# 009pcb6.net
KiCad netlist of a schematic drawn in EAGLE
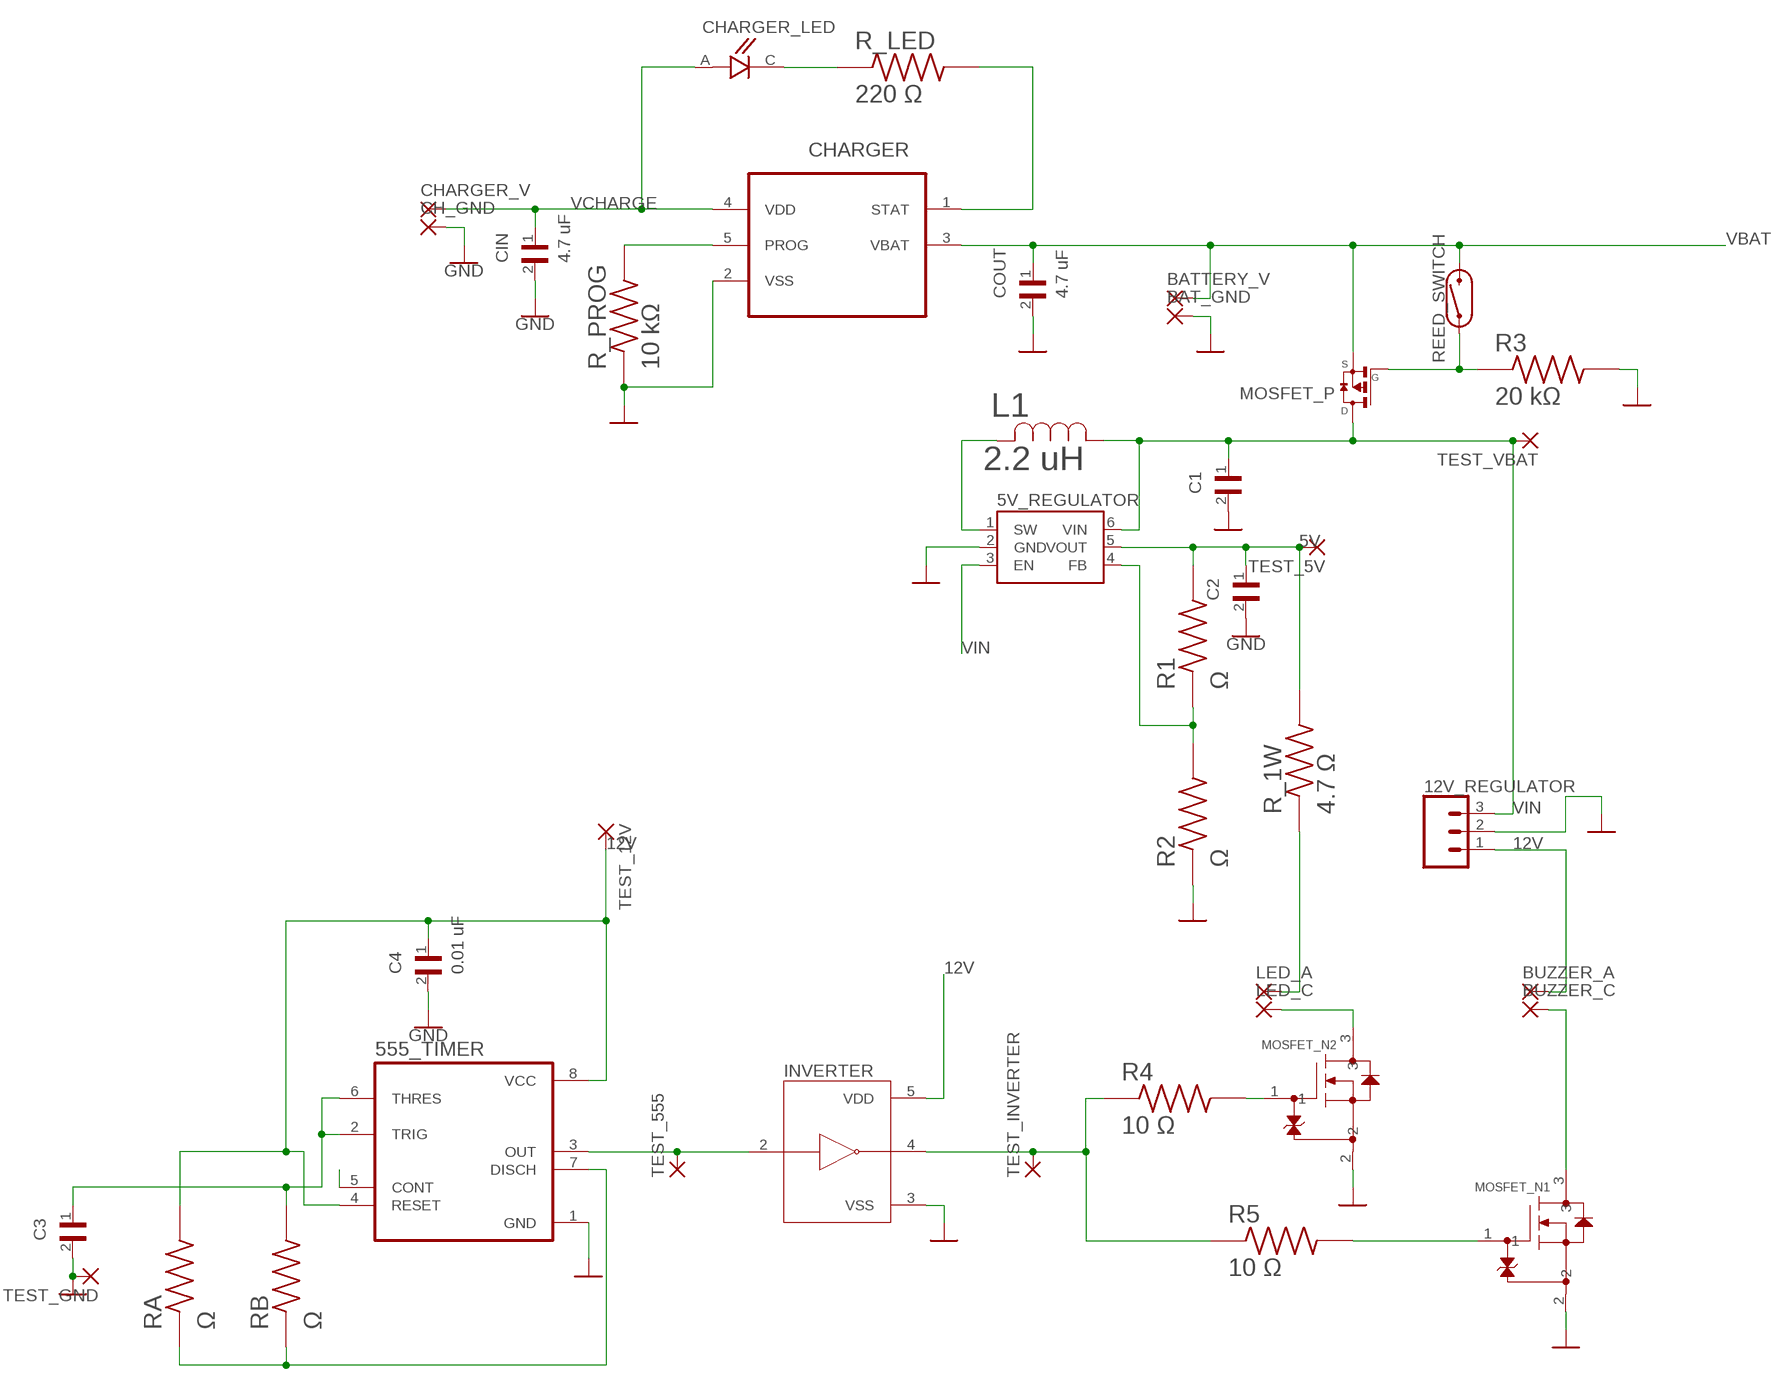
[diagram p0: schematic, sheet 1]

(export (version "E")
  (design (tool "Eeschema 10.0.6"))
  (components
    (comp (ref "5V_REGULATOR")
      (value "TLV61070ASOT-23")
      (footprint "eagle-import:SOT23-6")
      (libsource (lib "eagle-import") (part "TLV61070ASOT-23"))
    )
    (comp (ref "12V_REGULATOR")
      (value "CONN_03")
      (footprint "eagle-import:1X03")
      (libsource (lib "eagle-import") (part "CONN_03"))
    )
    (comp (ref "555_TIMER")
      (value "NE555DR")
      (footprint "eagle-import:SOIC127P599X175-8N")
      (fields (field (name "MF") "Texas Instruments"))
      (libsource (lib "eagle-import") (part "NE555DR"))
    )
    (comp (ref "BATTERY_V")
      (value "WIREPADSMD1,27-254")
      (footprint "eagle-import:SMD1,27-2,54")
      (libsource (lib "eagle-import") (part "WIREPADSMD1,27-254"))
    )
    (comp (ref "BAT_GND")
      (value "WIREPADSMD1,27-254")
      (footprint "eagle-import:SMD1,27-2,54")
      (libsource (lib "eagle-import") (part "WIREPADSMD1,27-254"))
    )
    (comp (ref "BUZZER_A")
      (value "WIREPADSMD1,27-254")
      (footprint "eagle-import:SMD1,27-2,54")
      (libsource (lib "eagle-import") (part "WIREPADSMD1,27-254"))
    )
    (comp (ref "BUZZER_C")
      (value "WIREPADSMD1,27-254")
      (footprint "eagle-import:SMD1,27-2,54")
      (libsource (lib "eagle-import") (part "WIREPADSMD1,27-254"))
    )
    (comp (ref "C1")
      (value "GRT21BR61H475ME13L")
      (footprint "eagle-import:CAPC2012X135N")
      (fields (field (name "MF") "Murata Electronics"))
      (libsource (lib "eagle-import") (part "GRT21BR61H475ME13L"))
    )
    (comp (ref "C2")
      (value "GRT21BR61H475ME13L")
      (footprint "eagle-import:CAPC2012X135N")
      (fields (field (name "MF") "Murata Electronics"))
      (libsource (lib "eagle-import") (part "GRT21BR61H475ME13L"))
    )
    (comp (ref "C3")
      (value "GRT21BR61H475ME13L")
      (footprint "eagle-import:CAPC2012X135N")
      (fields (field (name "MF") "Murata Electronics"))
      (libsource (lib "eagle-import") (part "GRT21BR61H475ME13L"))
    )
    (comp (ref "C4")
      (value "0.01 uF")
      (footprint "eagle-import:CAPC2012X135N")
      (fields (field (name "MF") "Murata Electronics") (field (name "MP") "GRT21BR61H475ME13L"))
      (libsource (lib "eagle-import") (part "GRT21BR61H475ME13L"))
    )
    (comp (ref "CHARGER")
      (value "MCP73831T-5ACI/OT")
      (footprint "eagle-import:SOT95P280X145-5N")
      (fields
        (field (name "DIGI-KEY_PART_NUMBER") "MCP73831T-5ACI/OTTR-ND")
        (field (name "MF") "Microchip Technology")
      )
      (libsource (lib "eagle-import") (part "MCP73831T-5ACI/OT"))
    )
    (comp (ref "CHARGER_LED")
      (value "5988170107F")
      (footprint "eagle-import:LEDC2012X70N")
      (fields (field (name "MF") "Dialight"))
      (libsource (lib "eagle-import") (part "5988170107F"))
    )
    (comp (ref "CHARGER_V")
      (value "WIREPADSMD1,27-254")
      (footprint "eagle-import:SMD1,27-2,54")
      (libsource (lib "eagle-import") (part "WIREPADSMD1,27-254"))
    )
    (comp (ref "CH_GND")
      (value "WIREPADSMD1,27-254")
      (footprint "eagle-import:SMD1,27-2,54")
      (libsource (lib "eagle-import") (part "WIREPADSMD1,27-254"))
    )
    (comp (ref "CIN")
      (value "4.7 uF")
      (footprint "eagle-import:CAPC2012X135N")
      (fields (field (name "MF") "Murata Electronics") (field (name "MP") "GRT21BR61H475ME13L"))
      (libsource (lib "eagle-import") (part "GRT21BR61H475ME13L"))
    )
    (comp (ref "COUT")
      (value "4.7 uF")
      (footprint "eagle-import:CAPC2012X135N")
      (fields (field (name "MF") "Murata Electronics") (field (name "MP") "GRT21BR61H475ME13L"))
      (libsource (lib "eagle-import") (part "GRT21BR61H475ME13L"))
    )
    (comp (ref "INVERTER")
      (value "BU4SU69G2-TR")
      (footprint "eagle-import:SOT95P280X125-5N")
      (fields (field (name "MF") "Rohm"))
      (libsource (lib "eagle-import") (part "BU4SU69G2-TR"))
    )
    (comp (ref "L1")
      (value "2.2 uH")
      (footprint "eagle-import:IND_8357022_WRE")
      (fields
        (field (name "MANUFACTURER_PART_NUMBER") "74438357022")
        (field (name "COPYRIGHT") "Copyright (C) 2022 Ultra Librarian. All rights reserved.")
      )
      (libsource (lib "eagle-import") (part "74438357022"))
    )
    (comp (ref "LED_A")
      (value "WIREPADSMD1,27-254")
      (footprint "eagle-import:SMD1,27-2,54")
      (libsource (lib "eagle-import") (part "WIREPADSMD1,27-254"))
    )
    (comp (ref "LED_C")
      (value "WIREPADSMD1,27-254")
      (footprint "eagle-import:SMD1,27-2,54")
      (libsource (lib "eagle-import") (part "WIREPADSMD1,27-254"))
    )
    (comp (ref "MOSFET_N1")
      (value "SSM3K335R")
      (footprint "eagle-import:SOT-23F_TOS")
      (fields (field (name "COPYRIGHT") "Copyright (C) 2022 Ultra Librarian. All rights reserved."))
      (libsource (lib "eagle-import") (part "SSM3K335R"))
    )
    (comp (ref "MOSFET_N2")
      (value "SSM3K335R")
      (footprint "eagle-import:SOT-23F_TOS")
      (fields (field (name "COPYRIGHT") "Copyright (C) 2022 Ultra Librarian. All rights reserved."))
      (libsource (lib "eagle-import") (part "SSM3K335R"))
    )
    (comp (ref "MOSFET_P")
      (value "DMP2004K")
      (footprint "eagle-import:SOT23")
      (fields (field (name "MF") "Diodes Zetex"))
      (libsource (lib "eagle-import") (part "DMP2004K"))
    )
    (comp (ref "R1")
      (value "Ω")
      (footprint "eagle-import:RESC2012X60N")
      (fields
        (field (name "DIGI-KEY_PART_NUMBER") "311-20KARTR-ND")
        (field (name "MF") "Yageo")
        (field (name "MP") "RC0805JR-0720KL")
      )
      (libsource (lib "eagle-import") (part "RC0805JR-0720KL"))
    )
    (comp (ref "R2")
      (value "Ω")
      (footprint "eagle-import:RESC2012X60N")
      (fields
        (field (name "DIGI-KEY_PART_NUMBER") "311-20KARTR-ND")
        (field (name "MF") "Yageo")
        (field (name "MP") "RC0805JR-0720KL")
      )
      (libsource (lib "eagle-import") (part "RC0805JR-0720KL"))
    )
    (comp (ref "R3")
      (value "20 kΩ")
      (footprint "eagle-import:RESC2012X60N")
      (fields
        (field (name "DIGI-KEY_PART_NUMBER") "311-20KARTR-ND")
        (field (name "MF") "Yageo")
        (field (name "MP") "RC0805JR-0720KL")
      )
      (libsource (lib "eagle-import") (part "RC0805JR-0720KL"))
    )
    (comp (ref "R4")
      (value "10 Ω")
      (footprint "eagle-import:RESC2012X60N")
      (fields
        (field (name "DIGI-KEY_PART_NUMBER") "311-20KARTR-ND")
        (field (name "MF") "Yageo")
        (field (name "MP") "RC0805JR-0720KL")
      )
      (libsource (lib "eagle-import") (part "RC0805JR-0720KL"))
    )
    (comp (ref "R5")
      (value "10 Ω")
      (footprint "eagle-import:RESC2012X60N")
      (fields
        (field (name "DIGI-KEY_PART_NUMBER") "311-20KARTR-ND")
        (field (name "MF") "Yageo")
        (field (name "MP") "RC0805JR-0720KL")
      )
      (libsource (lib "eagle-import") (part "RC0805JR-0720KL"))
    )
    (comp (ref "RA")
      (value "Ω")
      (footprint "eagle-import:RESC2012X60N")
      (fields
        (field (name "DIGI-KEY_PART_NUMBER") "311-20KARTR-ND")
        (field (name "MF") "Yageo")
        (field (name "MP") "RC0805JR-0720KL")
      )
      (libsource (lib "eagle-import") (part "RC0805JR-0720KL"))
    )
    (comp (ref "RB")
      (value "Ω")
      (footprint "eagle-import:RESC2012X60N")
      (fields
        (field (name "DIGI-KEY_PART_NUMBER") "311-20KARTR-ND")
        (field (name "MF") "Yageo")
        (field (name "MP") "RC0805JR-0720KL")
      )
      (libsource (lib "eagle-import") (part "RC0805JR-0720KL"))
    )
    (comp (ref "REED_SWITCH")
      (value "REED_SWITCH-PTH-GLASS")
      (footprint "eagle-import:REED_SWITCH_GLASS")
      (libsource (lib "eagle-import") (part "REED_SWITCH-PTH-GLASS"))
    )
    (comp (ref "R_1W")
      (value "4.7 Ω")
      (footprint "eagle-import:RESC6331X65N")
      (fields
        (field (name "DIGI-KEY_PART_NUMBER") "13-RC2512FK-074R7LTR-ND")
        (field (name "MF") "Yageo")
        (field (name "MP") "RC2512FK-074R7L")
      )
      (libsource (lib "eagle-import") (part "RC2512FK-074R7L"))
    )
    (comp (ref "R_LED")
      (value "220 Ω")
      (footprint "eagle-import:RESC2012X60N")
      (fields
        (field (name "DIGI-KEY_PART_NUMBER") "311-20KARTR-ND")
        (field (name "MF") "Yageo")
        (field (name "MP") "RC0805JR-0720KL")
      )
      (libsource (lib "eagle-import") (part "RC0805JR-0720KL"))
    )
    (comp (ref "R_PROG")
      (value "10 kΩ")
      (footprint "eagle-import:RESC2012X60N")
      (fields
        (field (name "DIGI-KEY_PART_NUMBER") "311-20KARTR-ND")
        (field (name "MF") "Yageo")
        (field (name "MP") "RC0805JR-0720KL")
      )
      (libsource (lib "eagle-import") (part "RC0805JR-0720KL"))
    )
    (comp (ref "TEST_5V")
      (value "WIREPADSMD1,27-254")
      (footprint "eagle-import:SMD1,27-2,54")
      (libsource (lib "eagle-import") (part "WIREPADSMD1,27-254"))
    )
    (comp (ref "TEST_12V")
      (value "WIREPADSMD1,27-254")
      (footprint "eagle-import:SMD1,27-2,54")
      (libsource (lib "eagle-import") (part "WIREPADSMD1,27-254"))
    )
    (comp (ref "TEST_555")
      (value "WIREPADSMD1,27-254")
      (footprint "eagle-import:SMD1,27-2,54")
      (libsource (lib "eagle-import") (part "WIREPADSMD1,27-254"))
    )
    (comp (ref "TEST_GND")
      (value "WIREPADSMD1,27-254")
      (footprint "eagle-import:SMD1,27-2,54")
      (libsource (lib "eagle-import") (part "WIREPADSMD1,27-254"))
    )
    (comp (ref "TEST_INVERTER")
      (value "WIREPADSMD1,27-254")
      (footprint "eagle-import:SMD1,27-2,54")
      (libsource (lib "eagle-import") (part "WIREPADSMD1,27-254"))
    )
    (comp (ref "TEST_VBAT")
      (value "WIREPADSMD1,27-254")
      (footprint "eagle-import:SMD1,27-2,54")
      (libsource (lib "eagle-import") (part "WIREPADSMD1,27-254"))
    )
  )
  (nets
    (net (code "1") (name "/5V") (class "Default")
      (node (ref "5V_REGULATOR") (pin "5") (pinfunction "VOUT_5") (pintype "bidirectional"))
      (node (ref "C2") (pin "1") (pinfunction "1_1") (pintype "passive"))
      (node (ref "R1") (pin "2") (pinfunction "2_2") (pintype "passive"))
      (node (ref "R_1W") (pin "2") (pinfunction "2_2") (pintype "passive"))
      (node (ref "TEST_5V") (pin "1") (pinfunction "P_1") (pintype "passive"))
    )
    (net (code "2") (name "/12V") (class "Default")
      (node (ref "12V_REGULATOR") (pin "1") (pinfunction "1_1") (pintype "passive"))
      (node (ref "555_TIMER") (pin "4") (pinfunction "RESET_4") (pintype "input"))
      (node (ref "555_TIMER") (pin "8") (pinfunction "VCC_8") (pintype "power_in"))
      (node (ref "BUZZER_A") (pin "1") (pinfunction "P_1") (pintype "passive"))
      (node (ref "C4") (pin "1") (pinfunction "1_1") (pintype "passive"))
      (node (ref "INVERTER") (pin "5") (pinfunction "VDD_5") (pintype "power_in"))
      (node (ref "RA") (pin "2") (pinfunction "2_2") (pintype "passive"))
      (node (ref "TEST_12V") (pin "1") (pinfunction "P_1") (pintype "passive"))
    )
    (net (code "3") (name "/VBAT") (class "Default")
      (node (ref "BATTERY_V") (pin "1") (pinfunction "P_1") (pintype "passive"))
      (node (ref "CHARGER") (pin "3") (pinfunction "VBAT_3") (pintype "output"))
      (node (ref "COUT") (pin "1") (pinfunction "1_1") (pintype "passive"))
      (node (ref "MOSFET_P") (pin "2") (pinfunction "S_2") (pintype "passive"))
      (node (ref "REED_SWITCH") (pin "P$2") (pinfunction "2_P$2") (pintype "passive"))
    )
    (net (code "4") (name "/VCHARGE") (class "Default")
      (node (ref "CHARGER") (pin "4") (pinfunction "VDD_4") (pintype "power_in"))
      (node (ref "CHARGER_LED") (pin "A") (pinfunction "A_A") (pintype "passive"))
      (node (ref "CHARGER_V") (pin "1") (pinfunction "P_1") (pintype "passive"))
      (node (ref "CIN") (pin "1") (pinfunction "1_1") (pintype "passive"))
    )
    (net (code "5") (name "/VIN") (class "Default")
      (node (ref "12V_REGULATOR") (pin "3") (pinfunction "3_3") (pintype "passive"))
      (node (ref "5V_REGULATOR") (pin "3") (pinfunction "EN_3") (pintype "bidirectional"))
      (node (ref "5V_REGULATOR") (pin "6") (pinfunction "VIN_6") (pintype "bidirectional"))
      (node (ref "C1") (pin "1") (pinfunction "1_1") (pintype "passive"))
      (node (ref "L1") (pin "1") (pinfunction "1_1") (pintype "passive"))
      (node (ref "MOSFET_P") (pin "3") (pinfunction "D_3") (pintype "passive"))
      (node (ref "TEST_VBAT") (pin "1") (pinfunction "P_1") (pintype "passive"))
    )
    (net (code "6") (name "GND") (class "Default")
      (node (ref "12V_REGULATOR") (pin "2") (pinfunction "2_2") (pintype "passive"))
      (node (ref "555_TIMER") (pin "1") (pinfunction "GND_1") (pintype "power_in"))
      (node (ref "5V_REGULATOR") (pin "2") (pinfunction "GND_2") (pintype "bidirectional"))
      (node (ref "BAT_GND") (pin "1") (pinfunction "P_1") (pintype "passive"))
      (node (ref "C1") (pin "2") (pinfunction "2_2") (pintype "passive"))
      (node (ref "C2") (pin "2") (pinfunction "2_2") (pintype "passive"))
      (node (ref "C3") (pin "2") (pinfunction "2_2") (pintype "passive"))
      (node (ref "C4") (pin "2") (pinfunction "2_2") (pintype "passive"))
      (node (ref "CHARGER") (pin "2") (pinfunction "VSS_2") (pintype "power_in"))
      (node (ref "CH_GND") (pin "1") (pinfunction "P_1") (pintype "passive"))
      (node (ref "CIN") (pin "2") (pinfunction "2_2") (pintype "passive"))
      (node (ref "COUT") (pin "2") (pinfunction "2_2") (pintype "passive"))
      (node (ref "INVERTER") (pin "3") (pinfunction "VSS_3") (pintype "power_in"))
      (node (ref "MOSFET_N1") (pin "2") (pinfunction "2_2") (pintype "passive"))
      (node (ref "MOSFET_N2") (pin "2") (pinfunction "2_2") (pintype "passive"))
      (node (ref "R2") (pin "1") (pinfunction "1_1") (pintype "passive"))
      (node (ref "R3") (pin "2") (pinfunction "2_2") (pintype "passive"))
      (node (ref "R_PROG") (pin "1") (pinfunction "1_1") (pintype "passive"))
      (node (ref "TEST_GND") (pin "1") (pinfunction "P_1") (pintype "passive"))
    )
    (net (code "7") (name "Net-(5V_REGULATOR-FB)") (class "Default")
      (node (ref "5V_REGULATOR") (pin "4") (pinfunction "FB_4") (pintype "bidirectional"))
      (node (ref "R1") (pin "1") (pinfunction "1_1") (pintype "passive"))
      (node (ref "R2") (pin "2") (pinfunction "2_2") (pintype "passive"))
    )
    (net (code "8") (name "Net-(5V_REGULATOR-SW)") (class "Default")
      (node (ref "5V_REGULATOR") (pin "1") (pinfunction "SW_1") (pintype "bidirectional"))
      (node (ref "L1") (pin "2") (pinfunction "2_2") (pintype "passive"))
    )
    (net (code "9") (name "Net-(555_TIMER-DISCH)") (class "Default")
      (node (ref "555_TIMER") (pin "7") (pinfunction "DISCH_7") (pintype "output"))
      (node (ref "RA") (pin "1") (pinfunction "1_1") (pintype "passive"))
      (node (ref "RB") (pin "1") (pinfunction "1_1") (pintype "passive"))
    )
    (net (code "10") (name "Net-(555_TIMER-OUT)") (class "Default")
      (node (ref "555_TIMER") (pin "3") (pinfunction "OUT_3") (pintype "output"))
      (node (ref "INVERTER") (pin "2") (pinfunction "A_2") (pintype "input"))
      (node (ref "TEST_555") (pin "1") (pinfunction "P_1") (pintype "passive"))
    )
    (net (code "11") (name "Net-(555_TIMER-THRES)") (class "Default")
      (node (ref "555_TIMER") (pin "2") (pinfunction "TRIG_2") (pintype "input"))
      (node (ref "555_TIMER") (pin "6") (pinfunction "THRES_6") (pintype "input"))
      (node (ref "C3") (pin "1") (pinfunction "1_1") (pintype "passive"))
      (node (ref "RB") (pin "2") (pinfunction "2_2") (pintype "passive"))
    )
    (net (code "12") (name "Net-(BUZZER_C-P)") (class "Default")
      (node (ref "BUZZER_C") (pin "1") (pinfunction "P_1") (pintype "passive"))
      (node (ref "MOSFET_N1") (pin "3") (pinfunction "3_3") (pintype "passive"))
    )
    (net (code "13") (name "Net-(CHARGER-PROG)") (class "Default")
      (node (ref "CHARGER") (pin "5") (pinfunction "PROG_5") (pintype "input"))
      (node (ref "R_PROG") (pin "2") (pinfunction "2_2") (pintype "passive"))
    )
    (net (code "14") (name "Net-(CHARGER-STAT)") (class "Default")
      (node (ref "CHARGER") (pin "1") (pinfunction "STAT_1") (pintype "output"))
      (node (ref "R_LED") (pin "2") (pinfunction "2_2") (pintype "passive"))
    )
    (net (code "15") (name "Net-(CHARGER_LED-PadC)") (class "Default")
      (node (ref "CHARGER_LED") (pin "C") (pinfunction "C_C") (pintype "passive"))
      (node (ref "R_LED") (pin "1") (pinfunction "1_1") (pintype "passive"))
    )
    (net (code "16") (name "Net-(INVERTER-Y)") (class "Default")
      (node (ref "INVERTER") (pin "4") (pinfunction "Y_4") (pintype "output"))
      (node (ref "R4") (pin "1") (pinfunction "1_1") (pintype "passive"))
      (node (ref "R5") (pin "1") (pinfunction "1_1") (pintype "passive"))
      (node (ref "TEST_INVERTER") (pin "1") (pinfunction "P_1") (pintype "passive"))
    )
    (net (code "17") (name "Net-(LED_A-P)") (class "Default")
      (node (ref "LED_A") (pin "1") (pinfunction "P_1") (pintype "passive"))
      (node (ref "R_1W") (pin "1") (pinfunction "1_1") (pintype "passive"))
    )
    (net (code "18") (name "Net-(LED_C-P)") (class "Default")
      (node (ref "LED_C") (pin "1") (pinfunction "P_1") (pintype "passive"))
      (node (ref "MOSFET_N2") (pin "3") (pinfunction "3_3") (pintype "passive"))
    )
    (net (code "19") (name "Net-(MOSFET_N1-Pad1)") (class "Default")
      (node (ref "MOSFET_N1") (pin "1") (pinfunction "1_1") (pintype "passive"))
      (node (ref "R5") (pin "2") (pinfunction "2_2") (pintype "passive"))
    )
    (net (code "20") (name "Net-(MOSFET_N2-Pad1)") (class "Default")
      (node (ref "MOSFET_N2") (pin "1") (pinfunction "1_1") (pintype "passive"))
      (node (ref "R4") (pin "2") (pinfunction "2_2") (pintype "passive"))
    )
    (net (code "21") (name "Net-(MOSFET_P-G)") (class "Default")
      (node (ref "MOSFET_P") (pin "1") (pinfunction "G_1") (pintype "passive"))
      (node (ref "R3") (pin "1") (pinfunction "1_1") (pintype "passive"))
      (node (ref "REED_SWITCH") (pin "P$1") (pinfunction "1_P$1") (pintype "passive"))
    )
    (net (code "22") (name "unconnected-(555_TIMER-CONT-Pad5)") (class "Default")
      (node (ref "555_TIMER") (pin "5") (pinfunction "CONT_5") (pintype "bidirectional"))
    )
  )
)
